# PIC18F14K50_USB.net
KiCad netlist of a schematic drawn in EAGLE
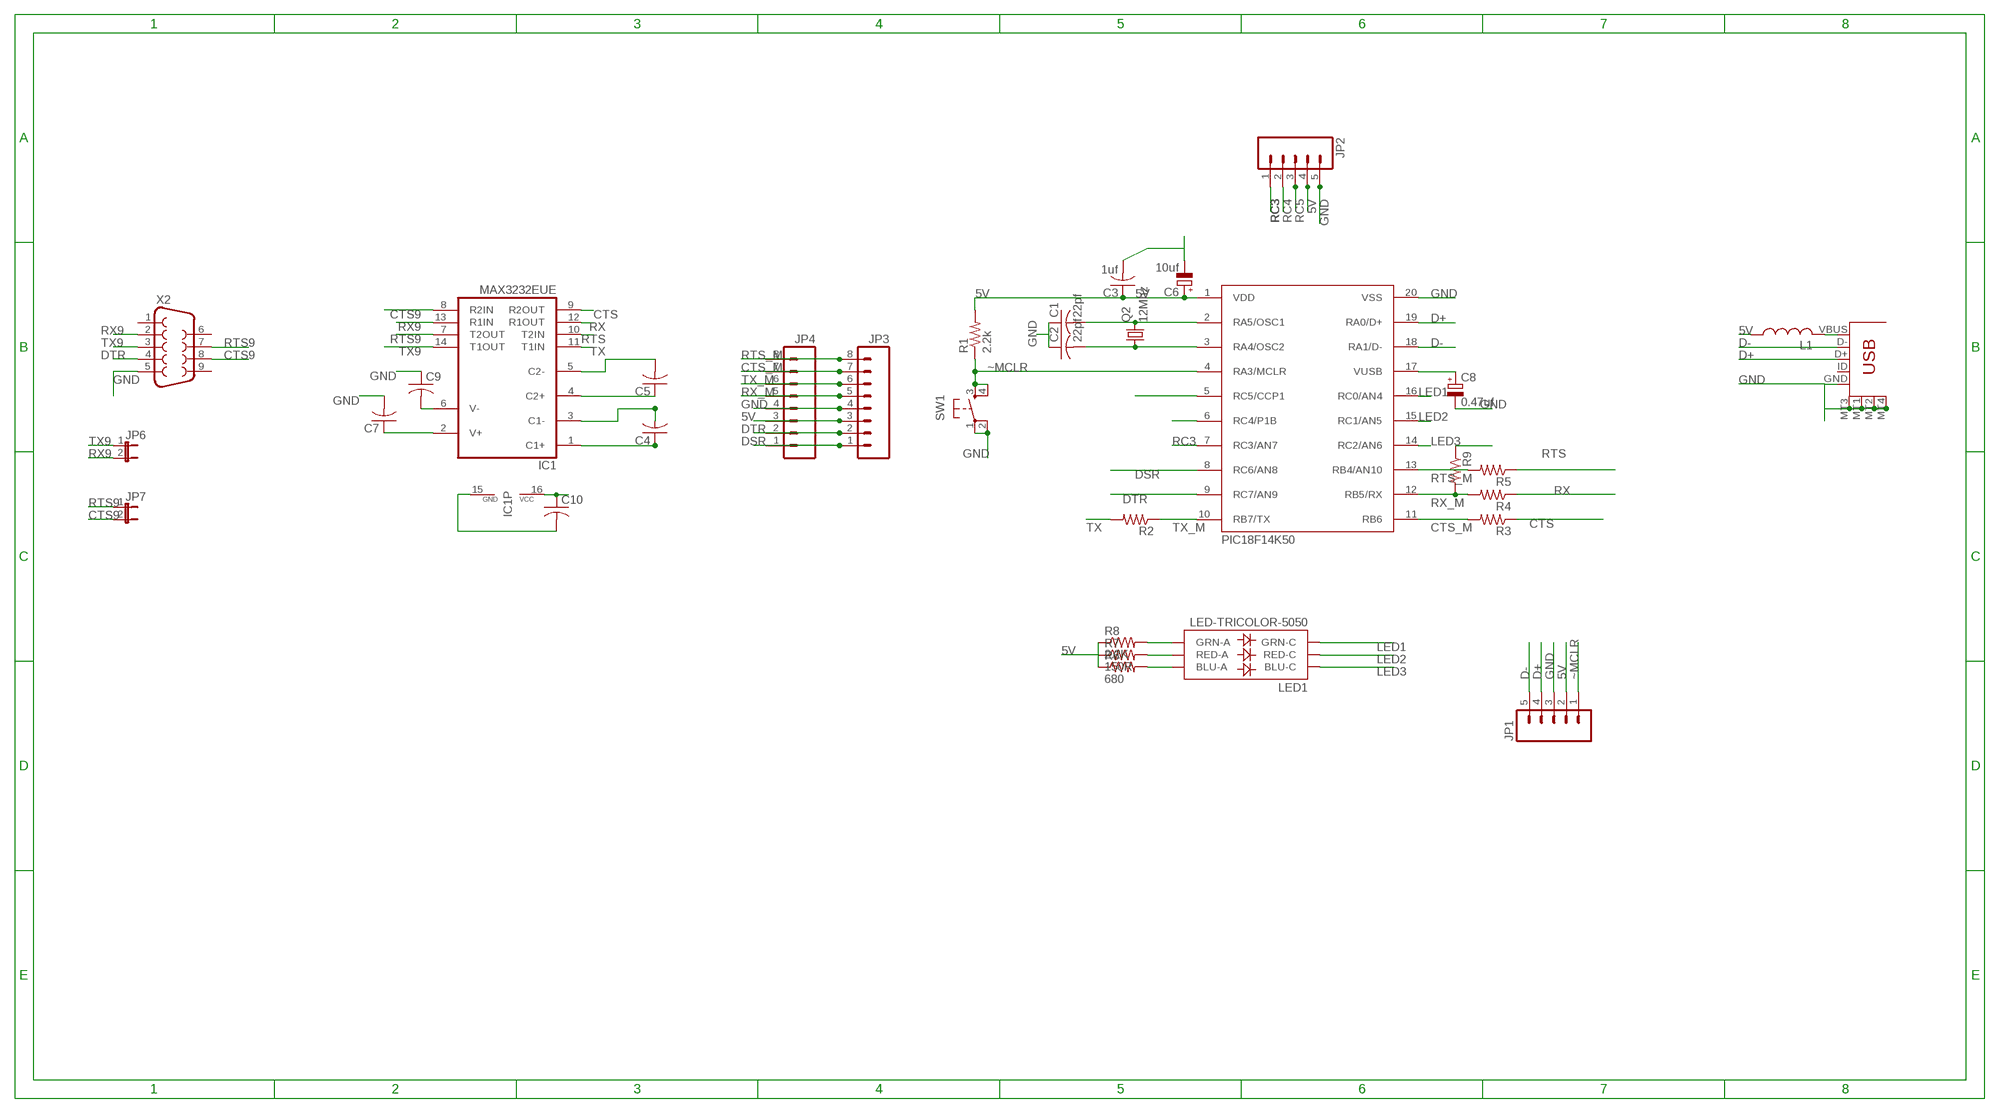
[diagram p0: schematic, sheet 1]

(export (version "E")
  (design (tool "Eeschema 10.0.6"))
  (components
    (comp (ref "C1")
      (value "22pf")
      (footprint "eagle-import:C0805")
      (libsource (lib "eagle-import") (part "C-USC0805"))
    )
    (comp (ref "C2")
      (value "22pf")
      (footprint "eagle-import:C0805")
      (libsource (lib "eagle-import") (part "C-USC0805"))
    )
    (comp (ref "C3")
      (value "1uf")
      (footprint "eagle-import:C0805")
      (libsource (lib "eagle-import") (part "C-USC0805"))
    )
    (comp (ref "C4")
      (value "C-USC0805")
      (footprint "eagle-import:C0805")
      (libsource (lib "eagle-import") (part "C-USC0805"))
    )
    (comp (ref "C5")
      (value "C-USC0805")
      (footprint "eagle-import:C0805")
      (libsource (lib "eagle-import") (part "C-USC0805"))
    )
    (comp (ref "C6")
      (value "10uf")
      (footprint "eagle-import:SMC_B")
      (libsource (lib "eagle-import") (part "CAP_POLSMC_B"))
    )
    (comp (ref "C7")
      (value "C-USC0805")
      (footprint "eagle-import:C0805")
      (libsource (lib "eagle-import") (part "C-USC0805"))
    )
    (comp (ref "C8")
      (value "0.47uf")
      (footprint "eagle-import:SMC_B")
      (libsource (lib "eagle-import") (part "CAP_POLSMC_B"))
    )
    (comp (ref "C9")
      (value "C-USC0805")
      (footprint "eagle-import:C0805")
      (libsource (lib "eagle-import") (part "C-USC0805"))
    )
    (comp (ref "C10")
      (value "C-USC0805")
      (footprint "eagle-import:C0805")
      (libsource (lib "eagle-import") (part "C-USC0805"))
    )
    (comp (ref "IC1")
      (value "MAX3232EUE")
      (footprint "eagle-import:TSSOP16")
      (fields (field (name "MF") "MAXIM") (field (name "MPN") "MAX3232EUE+"))
      (libsource (lib "eagle-import") (part "MAX3232UEE"))
    )
    (comp (ref "JP1")
      (value "M05PTH")
      (footprint "eagle-import:1X05")
      (libsource (lib "eagle-import") (part "M05PTH"))
    )
    (comp (ref "JP2")
      (value "M05PTH")
      (footprint "eagle-import:1X05")
      (libsource (lib "eagle-import") (part "M05PTH"))
    )
    (comp (ref "JP3")
      (value "M081X08")
      (footprint "eagle-import:1X08")
      (libsource (lib "eagle-import") (part "M081X08"))
    )
    (comp (ref "JP4")
      (value "M081X08")
      (footprint "eagle-import:1X08")
      (libsource (lib "eagle-import") (part "M081X08"))
    )
    (comp (ref "JP6")
      (value "JUMPER-2PTH")
      (footprint "eagle-import:1X02")
      (libsource (lib "eagle-import") (part "JUMPER-2PTH"))
    )
    (comp (ref "JP7")
      (value "JUMPER-2PTH")
      (footprint "eagle-import:1X02")
      (libsource (lib "eagle-import") (part "JUMPER-2PTH"))
    )
    (comp (ref "L1")
      (value "L-USL3225M")
      (footprint "eagle-import:L3225M")
      (libsource (lib "eagle-import") (part "L-USL3225M"))
    )
    (comp (ref "LED1")
      (value "LED-TRICOLOR-5050")
      (footprint "eagle-import:LED-TRICOLOR-5050")
      (libsource (lib "eagle-import") (part "LED-TRICOLOR-5050"))
    )
    (comp (ref "PIC18F14K50")
      (value "PIC18F14K50D")
      (footprint "eagle-import:SSOP20")
      (libsource (lib "eagle-import") (part "PIC18F14K50D"))
    )
    (comp (ref "Q2")
      (value "12Mhz")
      (footprint "eagle-import:HC49UP")
      (libsource (lib "eagle-import") (part "CRYSTALHC49UP"))
    )
    (comp (ref "R1")
      (value "2.2k")
      (footprint "eagle-import:M0805")
      (libsource (lib "eagle-import") (part "R-US_M0805"))
    )
    (comp (ref "R2")
      (value "R-US_M0805")
      (footprint "eagle-import:M0805")
      (libsource (lib "eagle-import") (part "R-US_M0805"))
    )
    (comp (ref "R3")
      (value "R-US_M0805")
      (footprint "eagle-import:M0805")
      (libsource (lib "eagle-import") (part "R-US_M0805"))
    )
    (comp (ref "R4")
      (value "R-US_M0805")
      (footprint "eagle-import:M0805")
      (libsource (lib "eagle-import") (part "R-US_M0805"))
    )
    (comp (ref "R5")
      (value "R-US_M0805")
      (footprint "eagle-import:M0805")
      (libsource (lib "eagle-import") (part "R-US_M0805"))
    )
    (comp (ref "R6")
      (value "680")
      (footprint "eagle-import:M0805")
      (libsource (lib "eagle-import") (part "R-US_M0805"))
    )
    (comp (ref "R7")
      (value "150R")
      (footprint "eagle-import:M0805")
      (libsource (lib "eagle-import") (part "R-US_M0805"))
    )
    (comp (ref "R8")
      (value "2.2K")
      (footprint "eagle-import:M0805")
      (libsource (lib "eagle-import") (part "R-US_M0805"))
    )
    (comp (ref "R9")
      (value "R-US_M0805")
      (footprint "eagle-import:M0805")
      (libsource (lib "eagle-import") (part "R-US_M0805"))
    )
    (comp (ref "SW1")
      (value "SW-SMD-SMALL")
      (footprint "eagle-import:TACT_SWITCH_SMALL")
      (libsource (lib "eagle-import") (part "SW-SMD-SMALL"))
    )
    (comp (ref "U$1")
      (value "USB-MICROB-HW-MC-5F")
      (footprint "eagle-import:USB-MICROB-HW-MC-5F-01")
      (libsource (lib "eagle-import") (part "USB-MICROB-HW-MC-5F"))
    )
    (comp (ref "X2")
      (value "F09D")
      (footprint "eagle-import:F09D")
      (libsource (lib "eagle-import") (part "F09D"))
    )
  )
  (nets
    (net (code "1") (name "/5V") (class "Default")
      (node (ref "C10") (pin "1") (pinfunction "1_1") (pintype "passive"))
      (node (ref "C3") (pin "1") (pinfunction "1_1") (pintype "passive"))
      (node (ref "C6") (pin "+") (pinfunction "+_+") (pintype "passive"))
      (node (ref "IC1") (pin "16") (pinfunction "VCC_16") (pintype "power_in"))
      (node (ref "JP1") (pin "2") (pinfunction "2_2") (pintype "passive"))
      (node (ref "JP2") (pin "4") (pinfunction "4_4") (pintype "passive"))
      (node (ref "JP3") (pin "3") (pinfunction "3_3") (pintype "passive"))
      (node (ref "JP4") (pin "3") (pinfunction "3_3") (pintype "passive"))
      (node (ref "L1") (pin "1") (pinfunction "1_1") (pintype "passive"))
      (node (ref "PIC18F14K50") (pin "1") (pinfunction "VDD_1") (pintype "bidirectional"))
      (node (ref "R1") (pin "2") (pinfunction "2_2") (pintype "passive"))
      (node (ref "R6") (pin "1") (pinfunction "1_1") (pintype "passive"))
      (node (ref "R7") (pin "1") (pinfunction "1_1") (pintype "passive"))
      (node (ref "R8") (pin "1") (pinfunction "1_1") (pintype "passive"))
      (node (ref "R9") (pin "1") (pinfunction "1_1") (pintype "passive"))
    )
    (net (code "2") (name "/CTS") (class "Default")
      (node (ref "IC1") (pin "9") (pinfunction "R2OUT_9") (pintype "output"))
      (node (ref "R3") (pin "1") (pinfunction "1_1") (pintype "passive"))
    )
    (net (code "3") (name "/CTS9") (class "Default")
      (node (ref "IC1") (pin "8") (pinfunction "R2IN_8") (pintype "input"))
      (node (ref "JP7") (pin "2") (pinfunction "2_2") (pintype "passive"))
      (node (ref "X2") (pin "8") (pinfunction "8_8") (pintype "passive"))
    )
    (net (code "4") (name "/CTS_M") (class "Default")
      (node (ref "JP3") (pin "7") (pinfunction "7_7") (pintype "passive"))
      (node (ref "JP4") (pin "7") (pinfunction "7_7") (pintype "passive"))
      (node (ref "PIC18F14K50") (pin "11") (pinfunction "RB6_11") (pintype "bidirectional"))
      (node (ref "R3") (pin "2") (pinfunction "2_2") (pintype "passive"))
    )
    (net (code "5") (name "/D+") (class "Default")
      (node (ref "JP1") (pin "4") (pinfunction "4_4") (pintype "passive"))
      (node (ref "PIC18F14K50") (pin "19") (pinfunction "RA0/D+_19") (pintype "bidirectional"))
      (node (ref "U$1") (pin "D+") (pinfunction "D+_D+") (pintype "bidirectional"))
    )
    (net (code "6") (name "/D-") (class "Default")
      (node (ref "JP1") (pin "5") (pinfunction "5_5") (pintype "passive"))
      (node (ref "PIC18F14K50") (pin "18") (pinfunction "RA1/D-_18") (pintype "bidirectional"))
      (node (ref "U$1") (pin "D-") (pinfunction "D-_D-") (pintype "bidirectional"))
    )
    (net (code "7") (name "/DSR") (class "Default")
      (node (ref "JP3") (pin "1") (pinfunction "1_1") (pintype "passive"))
      (node (ref "JP4") (pin "1") (pinfunction "1_1") (pintype "passive"))
      (node (ref "PIC18F14K50") (pin "8") (pinfunction "RC6/AN8_8") (pintype "bidirectional"))
    )
    (net (code "8") (name "/DTR") (class "Default")
      (node (ref "JP3") (pin "2") (pinfunction "2_2") (pintype "passive"))
      (node (ref "JP4") (pin "2") (pinfunction "2_2") (pintype "passive"))
      (node (ref "PIC18F14K50") (pin "9") (pinfunction "RC7/AN9_9") (pintype "bidirectional"))
      (node (ref "X2") (pin "4") (pinfunction "4_4") (pintype "passive"))
    )
    (net (code "9") (name "/GND") (class "Default")
      (node (ref "C1") (pin "1") (pinfunction "1_1") (pintype "passive"))
      (node (ref "C10") (pin "2") (pinfunction "2_2") (pintype "passive"))
      (node (ref "C2") (pin "1") (pinfunction "1_1") (pintype "passive"))
      (node (ref "C3") (pin "2") (pinfunction "2_2") (pintype "passive"))
      (node (ref "C6") (pin "-") (pinfunction "-_-") (pintype "passive"))
      (node (ref "C7") (pin "2") (pinfunction "2_2") (pintype "passive"))
      (node (ref "C8") (pin "-") (pinfunction "-_-") (pintype "passive"))
      (node (ref "C9") (pin "1") (pinfunction "1_1") (pintype "passive"))
      (node (ref "IC1") (pin "15") (pinfunction "GND_15") (pintype "power_in"))
      (node (ref "JP1") (pin "3") (pinfunction "3_3") (pintype "passive"))
      (node (ref "JP2") (pin "5") (pinfunction "5_5") (pintype "passive"))
      (node (ref "JP3") (pin "4") (pinfunction "4_4") (pintype "passive"))
      (node (ref "JP4") (pin "4") (pinfunction "4_4") (pintype "passive"))
      (node (ref "PIC18F14K50") (pin "20") (pinfunction "VSS_20") (pintype "bidirectional"))
      (node (ref "SW1") (pin "1") (pinfunction "1_1") (pintype "passive"))
      (node (ref "SW1") (pin "2") (pinfunction "2_2") (pintype "passive"))
      (node (ref "U$1") (pin "GND") (pinfunction "GND_GND") (pintype "bidirectional"))
      (node (ref "U$1") (pin "MT1") (pinfunction "MTN3_MT1") (pintype "bidirectional"))
      (node (ref "U$1") (pin "MT2") (pinfunction "MTN4_MT2") (pintype "bidirectional"))
      (node (ref "U$1") (pin "MT3") (pinfunction "MTN1_MT3") (pintype "bidirectional"))
      (node (ref "U$1") (pin "MT4") (pinfunction "MTN2_MT4") (pintype "bidirectional"))
      (node (ref "X2") (pin "5") (pinfunction "5_5") (pintype "passive"))
    )
    (net (code "10") (name "/LED1") (class "Default")
      (node (ref "LED1") (pin "3") (pinfunction "GRN-C_3") (pintype "bidirectional"))
      (node (ref "PIC18F14K50") (pin "16") (pinfunction "RC0/AN4_16") (pintype "bidirectional"))
    )
    (net (code "11") (name "/LED2") (class "Default")
      (node (ref "LED1") (pin "2") (pinfunction "RED-C_2") (pintype "bidirectional"))
      (node (ref "PIC18F14K50") (pin "15") (pinfunction "RC1/AN5_15") (pintype "bidirectional"))
    )
    (net (code "12") (name "/LED3") (class "Default")
      (node (ref "LED1") (pin "1") (pinfunction "BLU-C_1") (pintype "bidirectional"))
      (node (ref "PIC18F14K50") (pin "14") (pinfunction "RC2/AN6_14") (pintype "bidirectional"))
    )
    (net (code "13") (name "/RC3") (class "Default")
      (node (ref "JP2") (pin "1") (pinfunction "1_1") (pintype "passive"))
      (node (ref "PIC18F14K50") (pin "7") (pinfunction "RC3/AN7_7") (pintype "bidirectional"))
    )
    (net (code "14") (name "/RC4") (class "Default")
      (node (ref "JP2") (pin "2") (pinfunction "2_2") (pintype "passive"))
      (node (ref "PIC18F14K50") (pin "6") (pinfunction "RC4/P1B_6") (pintype "bidirectional"))
    )
    (net (code "15") (name "/RC5") (class "Default")
      (node (ref "JP2") (pin "3") (pinfunction "3_3") (pintype "passive"))
      (node (ref "PIC18F14K50") (pin "5") (pinfunction "RC5/CCP1_5") (pintype "bidirectional"))
    )
    (net (code "16") (name "/RTS") (class "Default")
      (node (ref "IC1") (pin "10") (pinfunction "T2IN_10") (pintype "input"))
      (node (ref "R5") (pin "1") (pinfunction "1_1") (pintype "passive"))
    )
    (net (code "17") (name "/RTS9") (class "Default")
      (node (ref "IC1") (pin "7") (pinfunction "T2OUT_7") (pintype "output"))
      (node (ref "JP7") (pin "1") (pinfunction "1_1") (pintype "passive"))
      (node (ref "X2") (pin "7") (pinfunction "7_7") (pintype "passive"))
    )
    (net (code "18") (name "/RTS_M") (class "Default")
      (node (ref "JP3") (pin "8") (pinfunction "8_8") (pintype "passive"))
      (node (ref "JP4") (pin "8") (pinfunction "8_8") (pintype "passive"))
      (node (ref "PIC18F14K50") (pin "13") (pinfunction "RB4/AN10_13") (pintype "bidirectional"))
      (node (ref "R5") (pin "2") (pinfunction "2_2") (pintype "passive"))
    )
    (net (code "19") (name "/RX") (class "Default")
      (node (ref "IC1") (pin "12") (pinfunction "R1OUT_12") (pintype "output"))
      (node (ref "R4") (pin "1") (pinfunction "1_1") (pintype "passive"))
    )
    (net (code "20") (name "/RX9") (class "Default")
      (node (ref "IC1") (pin "13") (pinfunction "R1IN_13") (pintype "input"))
      (node (ref "JP6") (pin "2") (pinfunction "2_2") (pintype "passive"))
      (node (ref "X2") (pin "2") (pinfunction "2_2") (pintype "passive"))
    )
    (net (code "21") (name "/RX_M") (class "Default")
      (node (ref "JP3") (pin "5") (pinfunction "5_5") (pintype "passive"))
      (node (ref "JP4") (pin "5") (pinfunction "5_5") (pintype "passive"))
      (node (ref "PIC18F14K50") (pin "12") (pinfunction "RB5/RX_12") (pintype "bidirectional"))
      (node (ref "R4") (pin "2") (pinfunction "2_2") (pintype "passive"))
      (node (ref "R9") (pin "2") (pinfunction "2_2") (pintype "passive"))
    )
    (net (code "22") (name "/TX") (class "Default")
      (node (ref "IC1") (pin "11") (pinfunction "T1IN_11") (pintype "input"))
      (node (ref "R2") (pin "2") (pinfunction "2_2") (pintype "passive"))
    )
    (net (code "23") (name "/TX9") (class "Default")
      (node (ref "IC1") (pin "14") (pinfunction "T1OUT_14") (pintype "output"))
      (node (ref "JP6") (pin "1") (pinfunction "1_1") (pintype "passive"))
      (node (ref "X2") (pin "3") (pinfunction "3_3") (pintype "passive"))
    )
    (net (code "24") (name "/TX_M") (class "Default")
      (node (ref "JP3") (pin "6") (pinfunction "6_6") (pintype "passive"))
      (node (ref "JP4") (pin "6") (pinfunction "6_6") (pintype "passive"))
      (node (ref "PIC18F14K50") (pin "10") (pinfunction "RB7/TX_10") (pintype "bidirectional"))
      (node (ref "R2") (pin "1") (pinfunction "1_1") (pintype "passive"))
    )
    (net (code "25") (name "/~{MCLR}") (class "Default")
      (node (ref "JP1") (pin "1") (pinfunction "1_1") (pintype "passive"))
      (node (ref "PIC18F14K50") (pin "4") (pinfunction "RA3/MCLR_4") (pintype "bidirectional"))
      (node (ref "R1") (pin "1") (pinfunction "1_1") (pintype "passive"))
      (node (ref "SW1") (pin "3") (pinfunction "3_3") (pintype "passive"))
      (node (ref "SW1") (pin "4") (pinfunction "4_4") (pintype "passive"))
    )
    (net (code "26") (name "Net-(IC1A-C1+)") (class "Default")
      (node (ref "C4") (pin "1") (pinfunction "1_1") (pintype "passive"))
      (node (ref "IC1") (pin "1") (pinfunction "C1+_1") (pintype "bidirectional"))
    )
    (net (code "27") (name "Net-(IC1A-C1-)") (class "Default")
      (node (ref "C4") (pin "2") (pinfunction "2_2") (pintype "passive"))
      (node (ref "IC1") (pin "3") (pinfunction "C1-_3") (pintype "bidirectional"))
    )
    (net (code "28") (name "Net-(IC1A-C2+)") (class "Default")
      (node (ref "C5") (pin "1") (pinfunction "1_1") (pintype "passive"))
      (node (ref "IC1") (pin "4") (pinfunction "C2+_4") (pintype "bidirectional"))
    )
    (net (code "29") (name "Net-(IC1A-C2-)") (class "Default")
      (node (ref "C5") (pin "2") (pinfunction "2_2") (pintype "passive"))
      (node (ref "IC1") (pin "5") (pinfunction "C2-_5") (pintype "bidirectional"))
    )
    (net (code "30") (name "Net-(IC1A-V+)") (class "Default")
      (node (ref "C7") (pin "1") (pinfunction "1_1") (pintype "passive"))
      (node (ref "IC1") (pin "2") (pinfunction "V+_2") (pintype "bidirectional"))
    )
    (net (code "31") (name "Net-(IC1A-V-)") (class "Default")
      (node (ref "C9") (pin "2") (pinfunction "2_2") (pintype "passive"))
      (node (ref "IC1") (pin "6") (pinfunction "V-_6") (pintype "bidirectional"))
    )
    (net (code "32") (name "Net-(L1-Pad2)") (class "Default")
      (node (ref "L1") (pin "2") (pinfunction "2_2") (pintype "passive"))
      (node (ref "U$1") (pin "VBUS") (pinfunction "VBUS_VBUS") (pintype "bidirectional"))
    )
    (net (code "33") (name "Net-(LED1-BLU-A)") (class "Default")
      (node (ref "LED1") (pin "6") (pinfunction "BLU-A_6") (pintype "bidirectional"))
      (node (ref "R6") (pin "2") (pinfunction "2_2") (pintype "passive"))
    )
    (net (code "34") (name "Net-(LED1-GRN-A)") (class "Default")
      (node (ref "LED1") (pin "4") (pinfunction "GRN-A_4") (pintype "bidirectional"))
      (node (ref "R8") (pin "2") (pinfunction "2_2") (pintype "passive"))
    )
    (net (code "35") (name "Net-(LED1-RED-A)") (class "Default")
      (node (ref "LED1") (pin "5") (pinfunction "RED-A_5") (pintype "bidirectional"))
      (node (ref "R7") (pin "2") (pinfunction "2_2") (pintype "passive"))
    )
    (net (code "36") (name "Net-(PIC18F14K50-RA4{slash}OSC2)") (class "Default")
      (node (ref "C2") (pin "2") (pinfunction "2_2") (pintype "passive"))
      (node (ref "PIC18F14K50") (pin "3") (pinfunction "RA4/OSC2_3") (pintype "bidirectional"))
      (node (ref "Q2") (pin "1") (pinfunction "1_1") (pintype "passive"))
    )
    (net (code "37") (name "Net-(PIC18F14K50-RA5{slash}OSC1)") (class "Default")
      (node (ref "C1") (pin "2") (pinfunction "2_2") (pintype "passive"))
      (node (ref "PIC18F14K50") (pin "2") (pinfunction "RA5/OSC1_2") (pintype "bidirectional"))
      (node (ref "Q2") (pin "2") (pinfunction "2_2") (pintype "passive"))
    )
    (net (code "38") (name "Net-(PIC18F14K50-VUSB)") (class "Default")
      (node (ref "C8") (pin "+") (pinfunction "+_+") (pintype "passive"))
      (node (ref "PIC18F14K50") (pin "17") (pinfunction "VUSB_17") (pintype "bidirectional"))
    )
    (net (code "39") (name "unconnected-(U$1-PadID)") (class "Default")
      (node (ref "U$1") (pin "ID") (pinfunction "ID_ID") (pintype "bidirectional"))
    )
    (net (code "40") (name "unconnected-(X2-Pad1)") (class "Default")
      (node (ref "X2") (pin "1") (pinfunction "1_1") (pintype "passive"))
    )
    (net (code "41") (name "unconnected-(X2-Pad6)") (class "Default")
      (node (ref "X2") (pin "6") (pinfunction "6_6") (pintype "passive"))
    )
    (net (code "42") (name "unconnected-(X2-Pad9)") (class "Default")
      (node (ref "X2") (pin "9") (pinfunction "9_9") (pintype "passive"))
    )
  )
)
